# PC104-52-52.net
KiCad netlist of a schematic drawn in Altium Designer
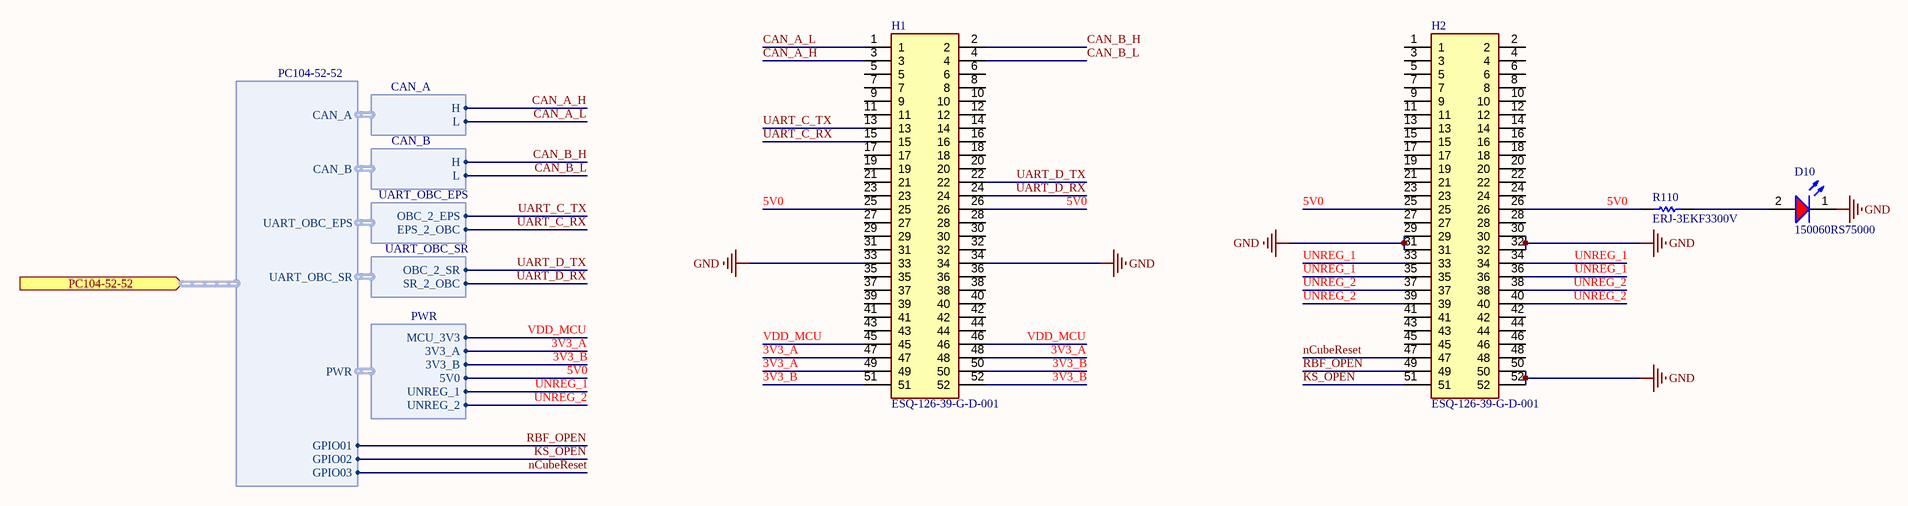
[diagram p0: PC104-52-52.SchDoc]

(export (version "E")
  (design (tool "Eeschema 10.0.6"))
  (components
    (comp (ref "D10")
      (value "150060RS75000")
      (footprint "WL-SMCW_0603_150060xx75000")
      (description "LED Low-Power Uni-Color Red 630nm 2V 2-Pin Chip 0603(1608Metric) T/R")
      (libsource (lib "Altium Content Vault") (part "LED_Red_2A-1K"))
    )
    (comp (ref "H1")
      (value "ESQ-126-39-G-D-001")
      (footprint "RHDR52W64P254_2X26_6654X495X1135P")
      (description "PC / 104 Connectors Elevated Socket Strip")
      (fields (field (name "MOUSER PART NUMBER") "200-ESQ12639GD001"))
      (libsource (lib "Hitesh Bhoyar") (part "ESQ-126-39-G-D-001"))
    )
    (comp (ref "H2")
      (value "ESQ-126-39-G-D-001")
      (footprint "RHDR52W64P254_2X26_6654X495X1135P")
      (description "PC / 104 Connectors Elevated Socket Strip")
      (fields (field (name "MOUSER PART NUMBER") "200-ESQ12639GD001"))
      (libsource (lib "Hitesh Bhoyar") (part "ESQ-126-39-G-D-001"))
    )
    (comp (ref "R110")
      (value "ERJ-3EKF3300V")
      (footprint "RESC1608X55X30LL15T15")
      (description "Chip Resistor, 330 Ohm, +/- 1%, 0.1 W, -55 to 155 degC, 0603 (1608 Metric), RoHS, Tape and Reel")
      (libsource (lib "Altium Content Vault") (part "RES-2"))
    )
  )
  (nets
    (net (code "7") (name "/3V3_A") (class "Default")
      (node (ref "H1") (pin "47") (pinfunction "47_47") (pintype "passive"))
      (node (ref "H1") (pin "48") (pinfunction "48_48") (pintype "passive"))
      (node (ref "H1") (pin "49") (pinfunction "49_49") (pintype "passive"))
    )
    (net (code "8") (name "/3V3_B") (class "Default")
      (node (ref "H1") (pin "50") (pinfunction "50_50") (pintype "passive"))
      (node (ref "H1") (pin "51") (pinfunction "51_51") (pintype "passive"))
      (node (ref "H1") (pin "52") (pinfunction "52_52") (pintype "passive"))
    )
    (net (code "9") (name "/5V0") (class "Default")
      (node (ref "H1") (pin "25") (pinfunction "25_25") (pintype "passive"))
      (node (ref "H1") (pin "26") (pinfunction "26_26") (pintype "passive"))
      (node (ref "H2") (pin "25") (pinfunction "25_25") (pintype "passive"))
      (node (ref "H2") (pin "26") (pinfunction "26_26") (pintype "passive"))
      (node (ref "R110") (pin "1") (pinfunction "1_1") (pintype "passive"))
    )
    (net (code "10") (name "/CAN_A_H") (class "Default")
      (node (ref "H1") (pin "3") (pinfunction "3_3") (pintype "passive"))
    )
    (net (code "11") (name "/CAN_A_L") (class "Default")
      (node (ref "H1") (pin "1") (pinfunction "1_1") (pintype "passive"))
    )
    (net (code "12") (name "/CAN_B_H") (class "Default")
      (node (ref "H1") (pin "2") (pinfunction "2_2") (pintype "passive"))
    )
    (net (code "13") (name "/CAN_B_L") (class "Default")
      (node (ref "H1") (pin "4") (pinfunction "4_4") (pintype "passive"))
    )
    (net (code "14") (name "/KS_OPEN") (class "Default")
      (node (ref "H2") (pin "51") (pinfunction "51_51") (pintype "passive"))
    )
    (net (code "16") (name "/RBF_OPEN") (class "Default")
      (node (ref "H2") (pin "49") (pinfunction "49_49") (pintype "passive"))
    )
    (net (code "17") (name "/UART_C_RX") (class "Default")
      (node (ref "H1") (pin "15") (pinfunction "15_15") (pintype "passive"))
    )
    (net (code "18") (name "/UART_C_TX") (class "Default")
      (node (ref "H1") (pin "13") (pinfunction "13_13") (pintype "passive"))
    )
    (net (code "19") (name "/UART_D_RX") (class "Default")
      (node (ref "H1") (pin "24") (pinfunction "24_24") (pintype "passive"))
    )
    (net (code "20") (name "/UART_D_TX") (class "Default")
      (node (ref "H1") (pin "22") (pinfunction "22_22") (pintype "passive"))
    )
    (net (code "21") (name "/UNREG_1") (class "Default")
      (node (ref "H2") (pin "33") (pinfunction "33_33") (pintype "passive"))
      (node (ref "H2") (pin "34") (pinfunction "34_34") (pintype "passive"))
      (node (ref "H2") (pin "35") (pinfunction "35_35") (pintype "passive"))
      (node (ref "H2") (pin "36") (pinfunction "36_36") (pintype "passive"))
    )
    (net (code "22") (name "/UNREG_2") (class "Default")
      (node (ref "H2") (pin "37") (pinfunction "37_37") (pintype "passive"))
      (node (ref "H2") (pin "38") (pinfunction "38_38") (pintype "passive"))
      (node (ref "H2") (pin "39") (pinfunction "39_39") (pintype "passive"))
      (node (ref "H2") (pin "40") (pinfunction "40_40") (pintype "passive"))
    )
    (net (code "23") (name "/VDD_MCU") (class "Default")
      (node (ref "H1") (pin "45") (pinfunction "45_45") (pintype "passive"))
      (node (ref "H1") (pin "46") (pinfunction "46_46") (pintype "passive"))
    )
    (net (code "24") (name "/nCubeReset") (class "Default")
      (node (ref "H2") (pin "47") (pinfunction "47_47") (pintype "passive"))
    )
    (net (code "30") (name "GND") (class "Default")
      (node (ref "D10") (pin "1") (pinfunction "K_1") (pintype "passive"))
      (node (ref "H1") (pin "33") (pinfunction "33_33") (pintype "passive"))
      (node (ref "H1") (pin "34") (pinfunction "34_34") (pintype "passive"))
      (node (ref "H2") (pin "29") (pinfunction "29_29") (pintype "passive"))
      (node (ref "H2") (pin "30") (pinfunction "30_30") (pintype "passive"))
      (node (ref "H2") (pin "31") (pinfunction "31_31") (pintype "passive"))
      (node (ref "H2") (pin "32") (pinfunction "32_32") (pintype "passive"))
      (node (ref "H2") (pin "50") (pinfunction "50_50") (pintype "passive"))
      (node (ref "H2") (pin "52") (pinfunction "52_52") (pintype "passive"))
    )
    (net (code "31") (name "Net-(D10-A)") (class "Default")
      (node (ref "D10") (pin "2") (pinfunction "A_2") (pintype "passive"))
      (node (ref "R110") (pin "2") (pinfunction "2_2") (pintype "passive"))
    )
    (net (code "32") (name "unconnected-(H1-Pad5)") (class "Default")
      (node (ref "H1") (pin "5") (pinfunction "5_5") (pintype "passive"))
    )
    (net (code "33") (name "unconnected-(H1-Pad6)") (class "Default")
      (node (ref "H1") (pin "6") (pinfunction "6_6") (pintype "passive"))
    )
    (net (code "34") (name "unconnected-(H1-Pad7)") (class "Default")
      (node (ref "H1") (pin "7") (pinfunction "7_7") (pintype "passive"))
    )
    (net (code "35") (name "unconnected-(H1-Pad8)") (class "Default")
      (node (ref "H1") (pin "8") (pinfunction "8_8") (pintype "passive"))
    )
    (net (code "36") (name "unconnected-(H1-Pad9)") (class "Default")
      (node (ref "H1") (pin "9") (pinfunction "9_9") (pintype "passive"))
    )
    (net (code "37") (name "unconnected-(H1-Pad10)") (class "Default")
      (node (ref "H1") (pin "10") (pinfunction "10_10") (pintype "passive"))
    )
    (net (code "38") (name "unconnected-(H1-Pad11)") (class "Default")
      (node (ref "H1") (pin "11") (pinfunction "11_11") (pintype "passive"))
    )
    (net (code "39") (name "unconnected-(H1-Pad12)") (class "Default")
      (node (ref "H1") (pin "12") (pinfunction "12_12") (pintype "passive"))
    )
    (net (code "40") (name "unconnected-(H1-Pad14)") (class "Default")
      (node (ref "H1") (pin "14") (pinfunction "14_14") (pintype "passive"))
    )
    (net (code "41") (name "unconnected-(H1-Pad16)") (class "Default")
      (node (ref "H1") (pin "16") (pinfunction "16_16") (pintype "passive"))
    )
    (net (code "42") (name "unconnected-(H1-Pad17)") (class "Default")
      (node (ref "H1") (pin "17") (pinfunction "17_17") (pintype "passive"))
    )
    (net (code "43") (name "unconnected-(H1-Pad18)") (class "Default")
      (node (ref "H1") (pin "18") (pinfunction "18_18") (pintype "passive"))
    )
    (net (code "44") (name "unconnected-(H1-Pad19)") (class "Default")
      (node (ref "H1") (pin "19") (pinfunction "19_19") (pintype "passive"))
    )
    (net (code "45") (name "unconnected-(H1-Pad20)") (class "Default")
      (node (ref "H1") (pin "20") (pinfunction "20_20") (pintype "passive"))
    )
    (net (code "46") (name "unconnected-(H1-Pad21)") (class "Default")
      (node (ref "H1") (pin "21") (pinfunction "21_21") (pintype "passive"))
    )
    (net (code "47") (name "unconnected-(H1-Pad23)") (class "Default")
      (node (ref "H1") (pin "23") (pinfunction "23_23") (pintype "passive"))
    )
    (net (code "48") (name "unconnected-(H1-Pad27)") (class "Default")
      (node (ref "H1") (pin "27") (pinfunction "27_27") (pintype "passive"))
    )
    (net (code "49") (name "unconnected-(H1-Pad28)") (class "Default")
      (node (ref "H1") (pin "28") (pinfunction "28_28") (pintype "passive"))
    )
    (net (code "50") (name "unconnected-(H1-Pad29)") (class "Default")
      (node (ref "H1") (pin "29") (pinfunction "29_29") (pintype "passive"))
    )
    (net (code "51") (name "unconnected-(H1-Pad30)") (class "Default")
      (node (ref "H1") (pin "30") (pinfunction "30_30") (pintype "passive"))
    )
    (net (code "52") (name "unconnected-(H1-Pad31)") (class "Default")
      (node (ref "H1") (pin "31") (pinfunction "31_31") (pintype "passive"))
    )
    (net (code "53") (name "unconnected-(H1-Pad32)") (class "Default")
      (node (ref "H1") (pin "32") (pinfunction "32_32") (pintype "passive"))
    )
    (net (code "54") (name "unconnected-(H1-Pad35)") (class "Default")
      (node (ref "H1") (pin "35") (pinfunction "35_35") (pintype "passive"))
    )
    (net (code "55") (name "unconnected-(H1-Pad36)") (class "Default")
      (node (ref "H1") (pin "36") (pinfunction "36_36") (pintype "passive"))
    )
    (net (code "56") (name "unconnected-(H1-Pad37)") (class "Default")
      (node (ref "H1") (pin "37") (pinfunction "37_37") (pintype "passive"))
    )
    (net (code "57") (name "unconnected-(H1-Pad38)") (class "Default")
      (node (ref "H1") (pin "38") (pinfunction "38_38") (pintype "passive"))
    )
    (net (code "58") (name "unconnected-(H1-Pad39)") (class "Default")
      (node (ref "H1") (pin "39") (pinfunction "39_39") (pintype "passive"))
    )
    (net (code "59") (name "unconnected-(H1-Pad40)") (class "Default")
      (node (ref "H1") (pin "40") (pinfunction "40_40") (pintype "passive"))
    )
    (net (code "60") (name "unconnected-(H1-Pad41)") (class "Default")
      (node (ref "H1") (pin "41") (pinfunction "41_41") (pintype "passive"))
    )
    (net (code "61") (name "unconnected-(H1-Pad42)") (class "Default")
      (node (ref "H1") (pin "42") (pinfunction "42_42") (pintype "passive"))
    )
    (net (code "62") (name "unconnected-(H1-Pad43)") (class "Default")
      (node (ref "H1") (pin "43") (pinfunction "43_43") (pintype "passive"))
    )
    (net (code "63") (name "unconnected-(H1-Pad44)") (class "Default")
      (node (ref "H1") (pin "44") (pinfunction "44_44") (pintype "passive"))
    )
    (net (code "64") (name "unconnected-(H2-Pad1)") (class "Default")
      (node (ref "H2") (pin "1") (pinfunction "1_1") (pintype "passive"))
    )
    (net (code "65") (name "unconnected-(H2-Pad2)") (class "Default")
      (node (ref "H2") (pin "2") (pinfunction "2_2") (pintype "passive"))
    )
    (net (code "66") (name "unconnected-(H2-Pad3)") (class "Default")
      (node (ref "H2") (pin "3") (pinfunction "3_3") (pintype "passive"))
    )
    (net (code "67") (name "unconnected-(H2-Pad4)") (class "Default")
      (node (ref "H2") (pin "4") (pinfunction "4_4") (pintype "passive"))
    )
    (net (code "68") (name "unconnected-(H2-Pad5)") (class "Default")
      (node (ref "H2") (pin "5") (pinfunction "5_5") (pintype "passive"))
    )
    (net (code "69") (name "unconnected-(H2-Pad6)") (class "Default")
      (node (ref "H2") (pin "6") (pinfunction "6_6") (pintype "passive"))
    )
    (net (code "70") (name "unconnected-(H2-Pad7)") (class "Default")
      (node (ref "H2") (pin "7") (pinfunction "7_7") (pintype "passive"))
    )
    (net (code "71") (name "unconnected-(H2-Pad8)") (class "Default")
      (node (ref "H2") (pin "8") (pinfunction "8_8") (pintype "passive"))
    )
    (net (code "72") (name "unconnected-(H2-Pad9)") (class "Default")
      (node (ref "H2") (pin "9") (pinfunction "9_9") (pintype "passive"))
    )
    (net (code "73") (name "unconnected-(H2-Pad10)") (class "Default")
      (node (ref "H2") (pin "10") (pinfunction "10_10") (pintype "passive"))
    )
    (net (code "74") (name "unconnected-(H2-Pad11)") (class "Default")
      (node (ref "H2") (pin "11") (pinfunction "11_11") (pintype "passive"))
    )
    (net (code "75") (name "unconnected-(H2-Pad12)") (class "Default")
      (node (ref "H2") (pin "12") (pinfunction "12_12") (pintype "passive"))
    )
    (net (code "76") (name "unconnected-(H2-Pad13)") (class "Default")
      (node (ref "H2") (pin "13") (pinfunction "13_13") (pintype "passive"))
    )
    (net (code "77") (name "unconnected-(H2-Pad14)") (class "Default")
      (node (ref "H2") (pin "14") (pinfunction "14_14") (pintype "passive"))
    )
    (net (code "78") (name "unconnected-(H2-Pad15)") (class "Default")
      (node (ref "H2") (pin "15") (pinfunction "15_15") (pintype "passive"))
    )
    (net (code "79") (name "unconnected-(H2-Pad16)") (class "Default")
      (node (ref "H2") (pin "16") (pinfunction "16_16") (pintype "passive"))
    )
    (net (code "80") (name "unconnected-(H2-Pad17)") (class "Default")
      (node (ref "H2") (pin "17") (pinfunction "17_17") (pintype "passive"))
    )
    (net (code "81") (name "unconnected-(H2-Pad18)") (class "Default")
      (node (ref "H2") (pin "18") (pinfunction "18_18") (pintype "passive"))
    )
    (net (code "82") (name "unconnected-(H2-Pad19)") (class "Default")
      (node (ref "H2") (pin "19") (pinfunction "19_19") (pintype "passive"))
    )
    (net (code "83") (name "unconnected-(H2-Pad20)") (class "Default")
      (node (ref "H2") (pin "20") (pinfunction "20_20") (pintype "passive"))
    )
    (net (code "84") (name "unconnected-(H2-Pad21)") (class "Default")
      (node (ref "H2") (pin "21") (pinfunction "21_21") (pintype "passive"))
    )
    (net (code "85") (name "unconnected-(H2-Pad22)") (class "Default")
      (node (ref "H2") (pin "22") (pinfunction "22_22") (pintype "passive"))
    )
    (net (code "86") (name "unconnected-(H2-Pad23)") (class "Default")
      (node (ref "H2") (pin "23") (pinfunction "23_23") (pintype "passive"))
    )
    (net (code "87") (name "unconnected-(H2-Pad24)") (class "Default")
      (node (ref "H2") (pin "24") (pinfunction "24_24") (pintype "passive"))
    )
    (net (code "88") (name "unconnected-(H2-Pad27)") (class "Default")
      (node (ref "H2") (pin "27") (pinfunction "27_27") (pintype "passive"))
    )
    (net (code "89") (name "unconnected-(H2-Pad28)") (class "Default")
      (node (ref "H2") (pin "28") (pinfunction "28_28") (pintype "passive"))
    )
    (net (code "90") (name "unconnected-(H2-Pad41)") (class "Default")
      (node (ref "H2") (pin "41") (pinfunction "41_41") (pintype "passive"))
    )
    (net (code "91") (name "unconnected-(H2-Pad42)") (class "Default")
      (node (ref "H2") (pin "42") (pinfunction "42_42") (pintype "passive"))
    )
    (net (code "92") (name "unconnected-(H2-Pad43)") (class "Default")
      (node (ref "H2") (pin "43") (pinfunction "43_43") (pintype "passive"))
    )
    (net (code "93") (name "unconnected-(H2-Pad44)") (class "Default")
      (node (ref "H2") (pin "44") (pinfunction "44_44") (pintype "passive"))
    )
    (net (code "94") (name "unconnected-(H2-Pad45)") (class "Default")
      (node (ref "H2") (pin "45") (pinfunction "45_45") (pintype "passive"))
    )
    (net (code "95") (name "unconnected-(H2-Pad46)") (class "Default")
      (node (ref "H2") (pin "46") (pinfunction "46_46") (pintype "passive"))
    )
    (net (code "96") (name "unconnected-(H2-Pad48)") (class "Default")
      (node (ref "H2") (pin "48") (pinfunction "48_48") (pintype "passive"))
    )
  )
)
